# cableado.net
KiCad netlist of a schematic drawn in EAGLE
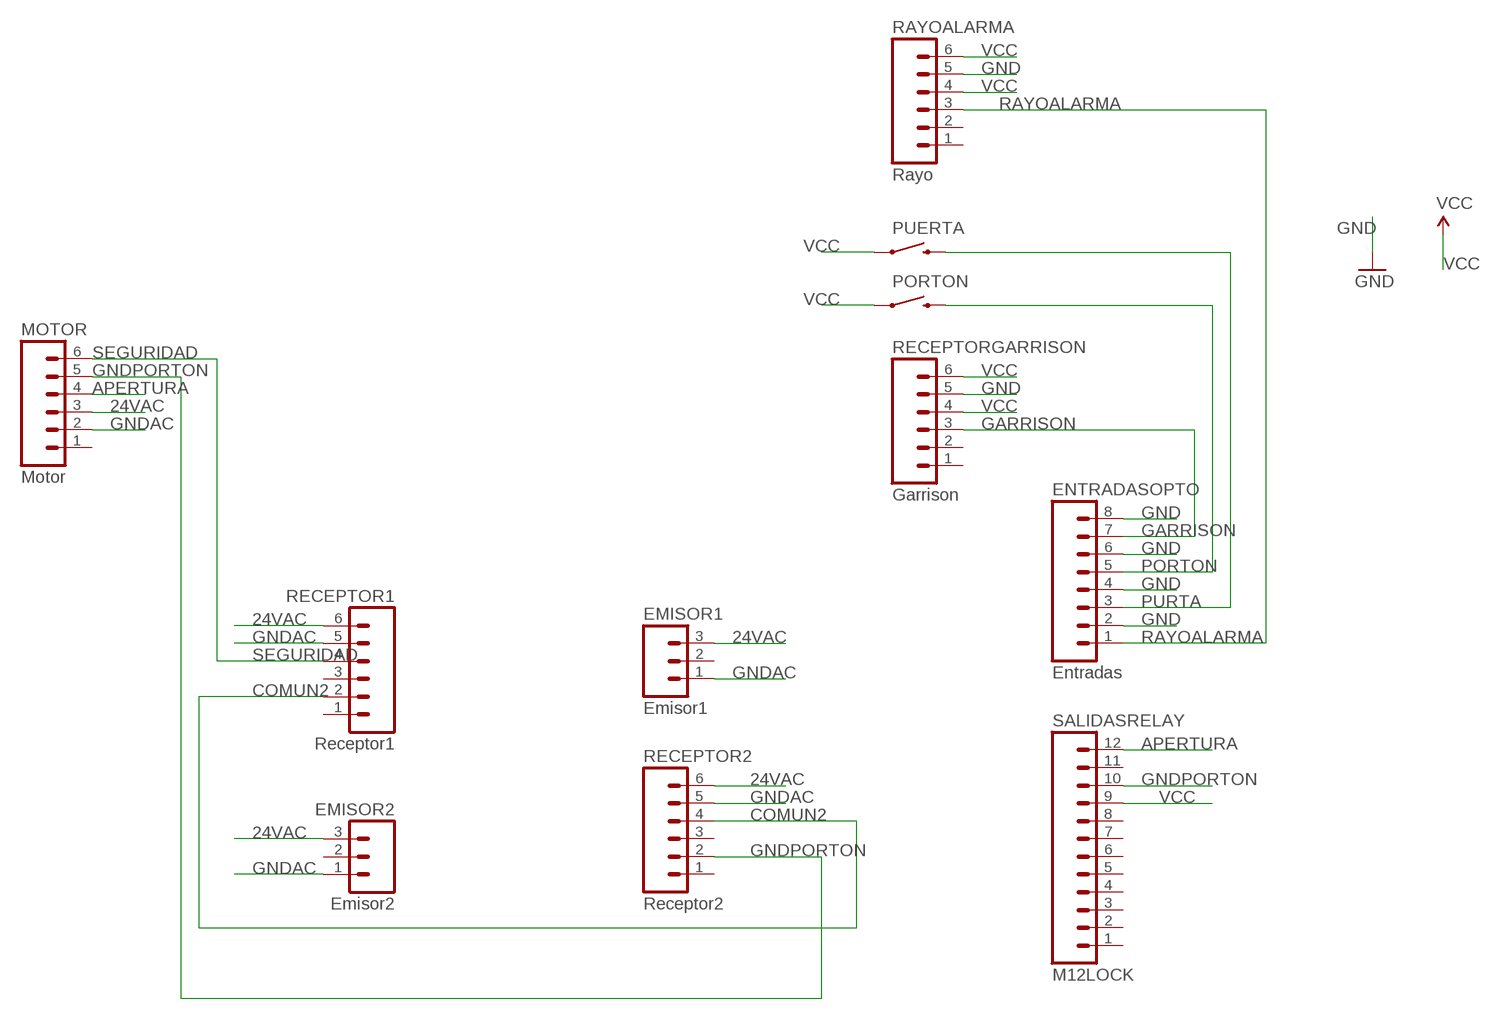
[diagram p0: schematic, sheet 1]

(export (version "E")
  (design (tool "Eeschema 10.0.6"))
  (components
    (comp (ref "EMISOR1")
      (value "Emisor1")
      (footprint "eagle-import:SCREWTERMINAL-5MM-3")
      (libsource (lib "eagle-import") (part "M03-SCREW-5MM"))
    )
    (comp (ref "EMISOR2")
      (value "Emisor2")
      (footprint "eagle-import:SCREWTERMINAL-5MM-3")
      (libsource (lib "eagle-import") (part "M03-SCREW-5MM"))
    )
    (comp (ref "ENTRADASOPTO")
      (value "Entradas")
      (footprint "eagle-import:SCREWTERMINAL-3.5MM-8")
      (libsource (lib "eagle-import") (part "M083.5MM-8"))
    )
    (comp (ref "MOTOR")
      (value "Motor")
      (footprint "eagle-import:MOLEX-1X6")
      (libsource (lib "eagle-import") (part "M06POLAR"))
    )
    (comp (ref "PORTON")
      (value "SWITCH-MOMENTARY-2-SMD-1101NE")
      (footprint "eagle-import:TACTILE-SWITCH-1101NE")
      (libsource (lib "eagle-import") (part "SWITCH-MOMENTARY-2-SMD-1101NE"))
    )
    (comp (ref "PUERTA")
      (value "SWITCH-MOMENTARY-2-SMD-1101NE")
      (footprint "eagle-import:TACTILE-SWITCH-1101NE")
      (libsource (lib "eagle-import") (part "SWITCH-MOMENTARY-2-SMD-1101NE"))
    )
    (comp (ref "RAYOALARMA")
      (value "Rayo")
      (footprint "eagle-import:MOLEX-1X6")
      (libsource (lib "eagle-import") (part "M06POLAR"))
    )
    (comp (ref "RECEPTOR1")
      (value "Receptor1")
      (footprint "eagle-import:MOLEX-1X6")
      (libsource (lib "eagle-import") (part "M06POLAR"))
    )
    (comp (ref "RECEPTOR2")
      (value "Receptor2")
      (footprint "eagle-import:MOLEX-1X6")
      (libsource (lib "eagle-import") (part "M06POLAR"))
    )
    (comp (ref "RECEPTORGARRISON")
      (value "Garrison")
      (footprint "eagle-import:MOLEX-1X6")
      (libsource (lib "eagle-import") (part "M06POLAR"))
    )
    (comp (ref "SALIDASRELAY")
      (value "M12LOCK")
      (footprint "eagle-import:1X12_LOCK")
      (libsource (lib "eagle-import") (part "M12LOCK"))
    )
  )
  (nets
    (net (code "1") (name "/24VAC") (class "Default")
      (node (ref "EMISOR1") (pin "3") (pinfunction "3_3") (pintype "passive"))
      (node (ref "EMISOR2") (pin "3") (pinfunction "3_3") (pintype "passive"))
      (node (ref "MOTOR") (pin "3") (pinfunction "3_3") (pintype "passive"))
      (node (ref "RECEPTOR1") (pin "6") (pinfunction "6_6") (pintype "passive"))
      (node (ref "RECEPTOR2") (pin "6") (pinfunction "6_6") (pintype "passive"))
    )
    (net (code "2") (name "/APERTURA") (class "Default")
      (node (ref "MOTOR") (pin "4") (pinfunction "4_4") (pintype "passive"))
      (node (ref "SALIDASRELAY") (pin "12") (pinfunction "12_12") (pintype "passive"))
    )
    (net (code "3") (name "/COMUN2") (class "Default")
      (node (ref "RECEPTOR1") (pin "2") (pinfunction "2_2") (pintype "passive"))
      (node (ref "RECEPTOR2") (pin "4") (pinfunction "4_4") (pintype "passive"))
    )
    (net (code "4") (name "/GARRISON") (class "Default")
      (node (ref "ENTRADASOPTO") (pin "7") (pinfunction "7_7") (pintype "passive"))
      (node (ref "RECEPTORGARRISON") (pin "3") (pinfunction "3_3") (pintype "passive"))
    )
    (net (code "5") (name "/GNDAC") (class "Default")
      (node (ref "EMISOR1") (pin "1") (pinfunction "1_1") (pintype "passive"))
      (node (ref "EMISOR2") (pin "1") (pinfunction "1_1") (pintype "passive"))
      (node (ref "MOTOR") (pin "2") (pinfunction "2_2") (pintype "passive"))
      (node (ref "RECEPTOR1") (pin "5") (pinfunction "5_5") (pintype "passive"))
      (node (ref "RECEPTOR2") (pin "5") (pinfunction "5_5") (pintype "passive"))
    )
    (net (code "6") (name "/GNDPORTON") (class "Default")
      (node (ref "MOTOR") (pin "5") (pinfunction "5_5") (pintype "passive"))
      (node (ref "RECEPTOR2") (pin "2") (pinfunction "2_2") (pintype "passive"))
      (node (ref "SALIDASRELAY") (pin "10") (pinfunction "10_10") (pintype "passive"))
    )
    (net (code "7") (name "/PORTON") (class "Default")
      (node (ref "ENTRADASOPTO") (pin "5") (pinfunction "5_5") (pintype "passive"))
      (node (ref "PORTON") (pin "2") (pinfunction "2_2") (pintype "passive"))
    )
    (net (code "8") (name "/PURTA") (class "Default")
      (node (ref "ENTRADASOPTO") (pin "3") (pinfunction "3_3") (pintype "passive"))
      (node (ref "PUERTA") (pin "2") (pinfunction "2_2") (pintype "passive"))
    )
    (net (code "9") (name "/RAYOALARMA") (class "Default")
      (node (ref "ENTRADASOPTO") (pin "1") (pinfunction "1_1") (pintype "passive"))
      (node (ref "RAYOALARMA") (pin "3") (pinfunction "3_3") (pintype "passive"))
    )
    (net (code "10") (name "/SEGURIDAD") (class "Default")
      (node (ref "MOTOR") (pin "6") (pinfunction "6_6") (pintype "passive"))
      (node (ref "RECEPTOR1") (pin "4") (pinfunction "4_4") (pintype "passive"))
    )
    (net (code "11") (name "GND") (class "Default")
      (node (ref "ENTRADASOPTO") (pin "2") (pinfunction "2_2") (pintype "passive"))
      (node (ref "ENTRADASOPTO") (pin "4") (pinfunction "4_4") (pintype "passive"))
      (node (ref "ENTRADASOPTO") (pin "6") (pinfunction "6_6") (pintype "passive"))
      (node (ref "ENTRADASOPTO") (pin "8") (pinfunction "8_8") (pintype "passive"))
      (node (ref "RAYOALARMA") (pin "5") (pinfunction "5_5") (pintype "passive"))
      (node (ref "RECEPTORGARRISON") (pin "5") (pinfunction "5_5") (pintype "passive"))
    )
    (net (code "12") (name "VCC") (class "Default")
      (node (ref "PORTON") (pin "1") (pinfunction "1_1") (pintype "passive"))
      (node (ref "PUERTA") (pin "1") (pinfunction "1_1") (pintype "passive"))
      (node (ref "RAYOALARMA") (pin "4") (pinfunction "4_4") (pintype "passive"))
      (node (ref "RAYOALARMA") (pin "6") (pinfunction "6_6") (pintype "passive"))
      (node (ref "RECEPTORGARRISON") (pin "4") (pinfunction "4_4") (pintype "passive"))
      (node (ref "RECEPTORGARRISON") (pin "6") (pinfunction "6_6") (pintype "passive"))
      (node (ref "SALIDASRELAY") (pin "9") (pinfunction "9_9") (pintype "passive"))
    )
    (net (code "13") (name "unconnected-(EMISOR1-Pad2)") (class "Default")
      (node (ref "EMISOR1") (pin "2") (pinfunction "2_2") (pintype "passive"))
    )
    (net (code "14") (name "unconnected-(EMISOR2-Pad2)") (class "Default")
      (node (ref "EMISOR2") (pin "2") (pinfunction "2_2") (pintype "passive"))
    )
    (net (code "15") (name "unconnected-(MOTOR-Pad1)") (class "Default")
      (node (ref "MOTOR") (pin "1") (pinfunction "1_1") (pintype "passive"))
    )
    (net (code "16") (name "unconnected-(RAYOALARMA-Pad1)") (class "Default")
      (node (ref "RAYOALARMA") (pin "1") (pinfunction "1_1") (pintype "passive"))
    )
    (net (code "17") (name "unconnected-(RAYOALARMA-Pad2)") (class "Default")
      (node (ref "RAYOALARMA") (pin "2") (pinfunction "2_2") (pintype "passive"))
    )
    (net (code "18") (name "unconnected-(RECEPTOR1-Pad1)") (class "Default")
      (node (ref "RECEPTOR1") (pin "1") (pinfunction "1_1") (pintype "passive"))
    )
    (net (code "19") (name "unconnected-(RECEPTOR1-Pad3)") (class "Default")
      (node (ref "RECEPTOR1") (pin "3") (pinfunction "3_3") (pintype "passive"))
    )
    (net (code "20") (name "unconnected-(RECEPTOR2-Pad1)") (class "Default")
      (node (ref "RECEPTOR2") (pin "1") (pinfunction "1_1") (pintype "passive"))
    )
    (net (code "21") (name "unconnected-(RECEPTOR2-Pad3)") (class "Default")
      (node (ref "RECEPTOR2") (pin "3") (pinfunction "3_3") (pintype "passive"))
    )
    (net (code "22") (name "unconnected-(RECEPTORGARRISON-Pad1)") (class "Default")
      (node (ref "RECEPTORGARRISON") (pin "1") (pinfunction "1_1") (pintype "passive"))
    )
    (net (code "23") (name "unconnected-(RECEPTORGARRISON-Pad2)") (class "Default")
      (node (ref "RECEPTORGARRISON") (pin "2") (pinfunction "2_2") (pintype "passive"))
    )
    (net (code "24") (name "unconnected-(SALIDASRELAY-Pad1)") (class "Default")
      (node (ref "SALIDASRELAY") (pin "1") (pinfunction "1_1") (pintype "passive"))
    )
    (net (code "25") (name "unconnected-(SALIDASRELAY-Pad2)") (class "Default")
      (node (ref "SALIDASRELAY") (pin "2") (pinfunction "2_2") (pintype "passive"))
    )
    (net (code "26") (name "unconnected-(SALIDASRELAY-Pad3)") (class "Default")
      (node (ref "SALIDASRELAY") (pin "3") (pinfunction "3_3") (pintype "passive"))
    )
    (net (code "27") (name "unconnected-(SALIDASRELAY-Pad4)") (class "Default")
      (node (ref "SALIDASRELAY") (pin "4") (pinfunction "4_4") (pintype "passive"))
    )
    (net (code "28") (name "unconnected-(SALIDASRELAY-Pad5)") (class "Default")
      (node (ref "SALIDASRELAY") (pin "5") (pinfunction "5_5") (pintype "passive"))
    )
    (net (code "29") (name "unconnected-(SALIDASRELAY-Pad6)") (class "Default")
      (node (ref "SALIDASRELAY") (pin "6") (pinfunction "6_6") (pintype "passive"))
    )
    (net (code "30") (name "unconnected-(SALIDASRELAY-Pad7)") (class "Default")
      (node (ref "SALIDASRELAY") (pin "7") (pinfunction "7_7") (pintype "passive"))
    )
    (net (code "31") (name "unconnected-(SALIDASRELAY-Pad8)") (class "Default")
      (node (ref "SALIDASRELAY") (pin "8") (pinfunction "8_8") (pintype "passive"))
    )
    (net (code "32") (name "unconnected-(SALIDASRELAY-Pad11)") (class "Default")
      (node (ref "SALIDASRELAY") (pin "11") (pinfunction "11_11") (pintype "passive"))
    )
  )
)
